# BrainA1-12n8.net
KiCad netlist of a schematic drawn in EAGLE
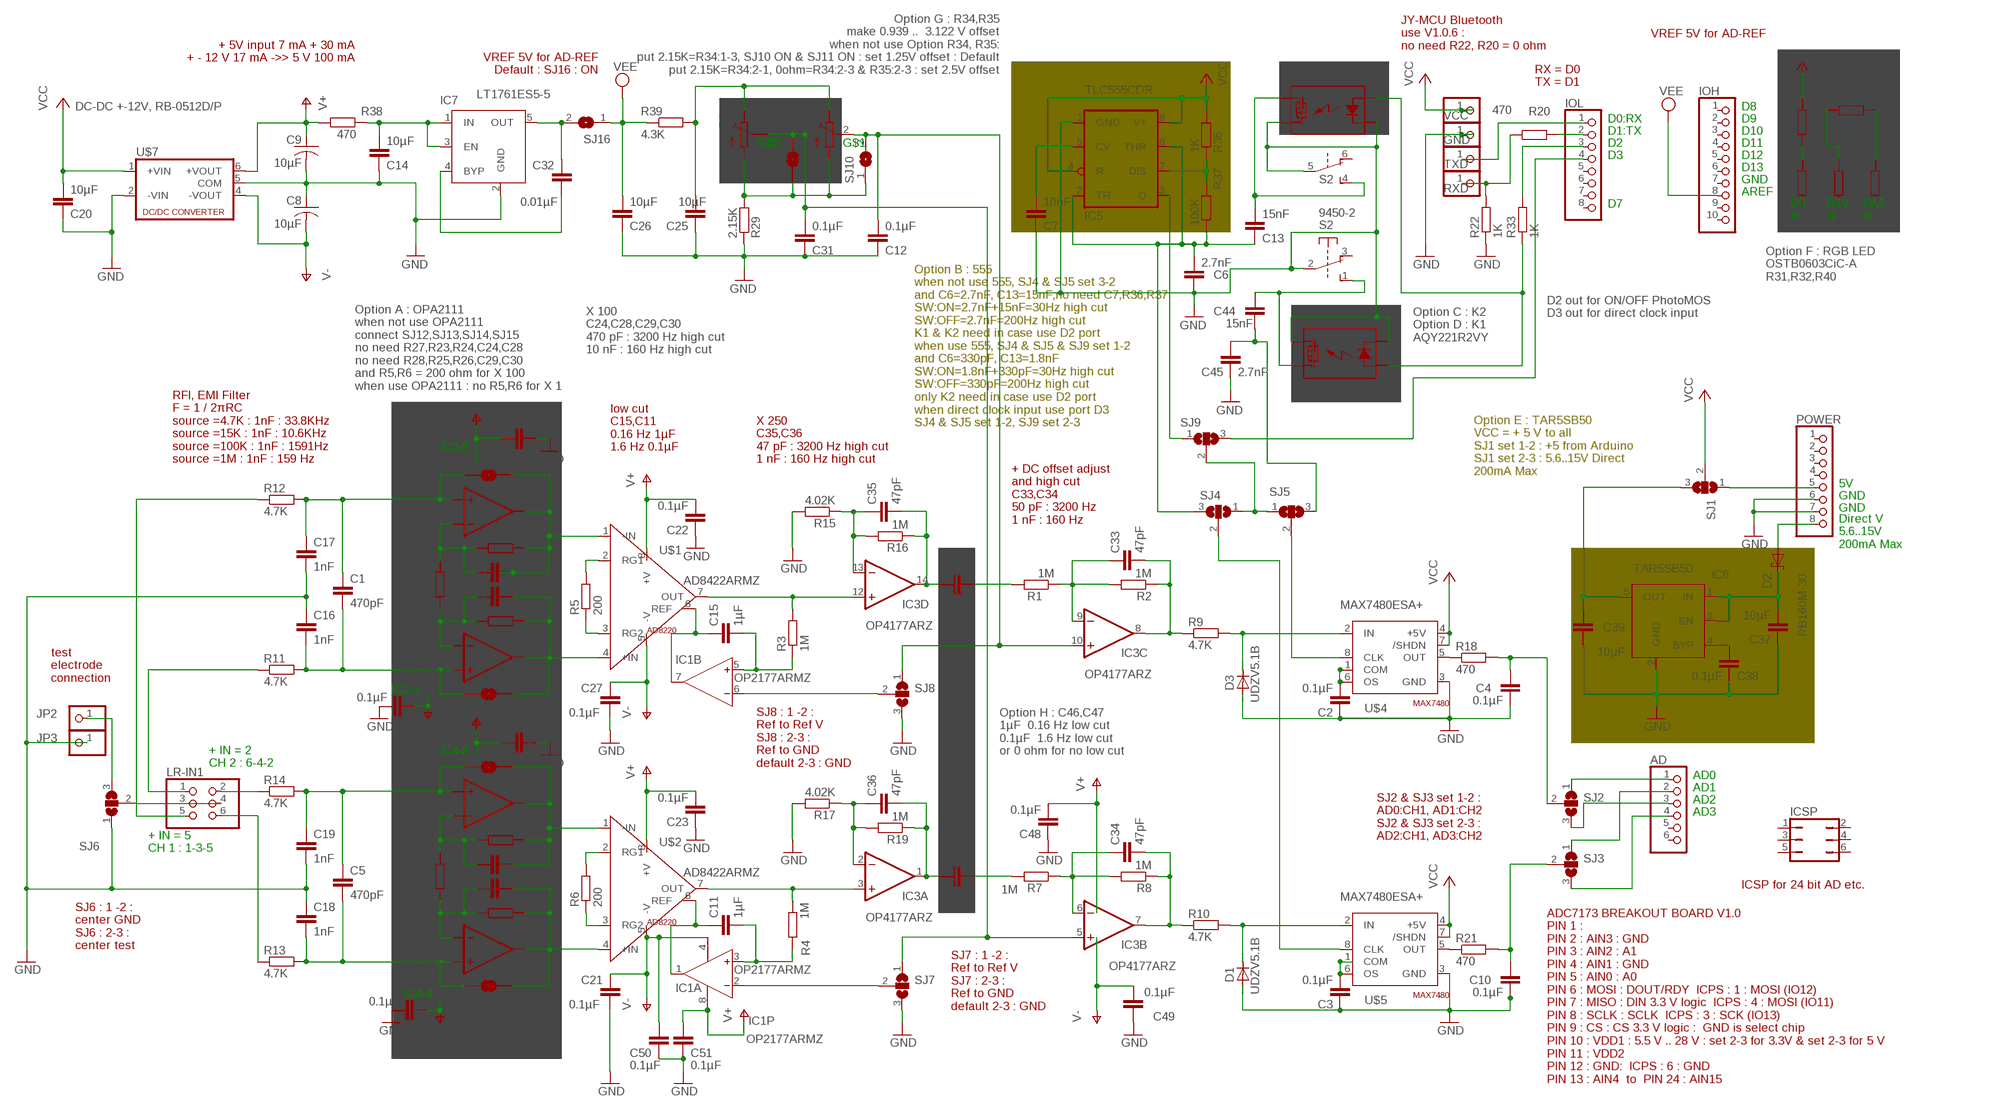
[diagram p0: schematic, sheet 1]

(export (version "E")
  (design (tool "Eeschema 10.0.6"))
  (components
    (comp (ref "AD")
      (value "PINHD-1X6")
      (footprint "eagle-import:1X06")
      (libsource (lib "eagle-import") (part "PINHD-1X6"))
    )
    (comp (ref "C1")
      (value "470pF")
      (footprint "eagle-import:C0805")
      (libsource (lib "eagle-import") (part "C-EUC0805"))
    )
    (comp (ref "C2")
      (value "0.1µF")
      (footprint "eagle-import:C0805")
      (libsource (lib "eagle-import") (part "C-EUC0805"))
    )
    (comp (ref "C3")
      (value "0.1µF")
      (footprint "eagle-import:C0805")
      (libsource (lib "eagle-import") (part "C-EUC0805"))
    )
    (comp (ref "C4")
      (value "0.1µF")
      (footprint "eagle-import:C0805")
      (libsource (lib "eagle-import") (part "C-EUC0805"))
    )
    (comp (ref "C5")
      (value "470pF")
      (footprint "eagle-import:C0805")
      (libsource (lib "eagle-import") (part "C-EUC0805"))
    )
    (comp (ref "C6")
      (value "2.7nF")
      (footprint "eagle-import:C0805")
      (libsource (lib "eagle-import") (part "C-EUC0805"))
    )
    (comp (ref "C7")
      (value "10nF")
      (footprint "eagle-import:C0805")
      (libsource (lib "eagle-import") (part "C-EUC0805"))
    )
    (comp (ref "C8")
      (value "10µF")
      (footprint "eagle-import:C0805")
      (libsource (lib "eagle-import") (part "C-USC0805"))
    )
    (comp (ref "C9")
      (value "10µF")
      (footprint "eagle-import:C0805")
      (libsource (lib "eagle-import") (part "C-USC0805"))
    )
    (comp (ref "C10")
      (value "0.1µF")
      (footprint "eagle-import:C0805")
      (libsource (lib "eagle-import") (part "C-EUC0805"))
    )
    (comp (ref "C11")
      (value "1µF")
      (footprint "eagle-import:C0805")
      (libsource (lib "eagle-import") (part "C-EUC0805"))
    )
    (comp (ref "C12")
      (value "0.1µF")
      (footprint "eagle-import:C0805")
      (libsource (lib "eagle-import") (part "C-EUC0805"))
    )
    (comp (ref "C13")
      (value "15nF")
      (footprint "eagle-import:C0805")
      (libsource (lib "eagle-import") (part "C-EUC0805"))
    )
    (comp (ref "C14")
      (value "10µF")
      (footprint "eagle-import:C0805")
      (libsource (lib "eagle-import") (part "C-EUC0805"))
    )
    (comp (ref "C15")
      (value "1µF")
      (footprint "eagle-import:C0805")
      (libsource (lib "eagle-import") (part "C-EUC0805"))
    )
    (comp (ref "C16")
      (value "1nF")
      (footprint "eagle-import:C0805")
      (libsource (lib "eagle-import") (part "C-EUC0805"))
    )
    (comp (ref "C17")
      (value "1nF")
      (footprint "eagle-import:C0805")
      (libsource (lib "eagle-import") (part "C-EUC0805"))
    )
    (comp (ref "C18")
      (value "1nF")
      (footprint "eagle-import:C0805")
      (libsource (lib "eagle-import") (part "C-EUC0805"))
    )
    (comp (ref "C19")
      (value "1nF")
      (footprint "eagle-import:C0805")
      (libsource (lib "eagle-import") (part "C-EUC0805"))
    )
    (comp (ref "C20")
      (value "10µF")
      (footprint "eagle-import:C0805")
      (libsource (lib "eagle-import") (part "C-EUC0805"))
    )
    (comp (ref "C21")
      (value "0.1µF")
      (footprint "eagle-import:C0805")
      (libsource (lib "eagle-import") (part "C-EUC0805"))
    )
    (comp (ref "C22")
      (value "0.1µF")
      (footprint "eagle-import:C0805")
      (libsource (lib "eagle-import") (part "C-EUC0805"))
    )
    (comp (ref "C23")
      (value "0.1µF")
      (footprint "eagle-import:C0805")
      (libsource (lib "eagle-import") (part "C-EUC0805"))
    )
    (comp (ref "C24")
      (value "470pF")
      (footprint "eagle-import:C0805")
      (libsource (lib "eagle-import") (part "C-EUC0805"))
    )
    (comp (ref "C25")
      (value "10µF")
      (footprint "eagle-import:C0805")
      (libsource (lib "eagle-import") (part "C-EUC0805"))
    )
    (comp (ref "C26")
      (value "10µF")
      (footprint "eagle-import:C0805")
      (libsource (lib "eagle-import") (part "C-EUC0805"))
    )
    (comp (ref "C27")
      (value "0.1µF")
      (footprint "eagle-import:C0805")
      (libsource (lib "eagle-import") (part "C-EUC0805"))
    )
    (comp (ref "C28")
      (value "470pF")
      (footprint "eagle-import:C0805")
      (libsource (lib "eagle-import") (part "C-EUC0805"))
    )
    (comp (ref "C29")
      (value "470pF")
      (footprint "eagle-import:C0805")
      (libsource (lib "eagle-import") (part "C-EUC0805"))
    )
    (comp (ref "C30")
      (value "470pF")
      (footprint "eagle-import:C0805")
      (libsource (lib "eagle-import") (part "C-EUC0805"))
    )
    (comp (ref "C31")
      (value "0.1µF")
      (footprint "eagle-import:C0805")
      (libsource (lib "eagle-import") (part "C-EUC0805"))
    )
    (comp (ref "C32")
      (value "0.01µF")
      (footprint "eagle-import:C0805")
      (libsource (lib "eagle-import") (part "C-EUC0805"))
    )
    (comp (ref "C33")
      (value "47pF")
      (footprint "eagle-import:C0805")
      (libsource (lib "eagle-import") (part "C-EUC0805"))
    )
    (comp (ref "C34")
      (value "47pF")
      (footprint "eagle-import:C0805")
      (libsource (lib "eagle-import") (part "C-EUC0805"))
    )
    (comp (ref "C35")
      (value "47pF")
      (footprint "eagle-import:C0805")
      (libsource (lib "eagle-import") (part "C-EUC0805"))
    )
    (comp (ref "C36")
      (value "47pF")
      (footprint "eagle-import:C0805")
      (libsource (lib "eagle-import") (part "C-EUC0805"))
    )
    (comp (ref "C37")
      (value "10µF")
      (footprint "eagle-import:C0805")
      (libsource (lib "eagle-import") (part "C-EUC0805"))
    )
    (comp (ref "C38")
      (value "0.1µF")
      (footprint "eagle-import:C0805")
      (libsource (lib "eagle-import") (part "C-EUC0805"))
    )
    (comp (ref "C39")
      (value "10µF")
      (footprint "eagle-import:C0805")
      (libsource (lib "eagle-import") (part "C-EUC0805"))
    )
    (comp (ref "C40")
      (value "0.1µF")
      (footprint "eagle-import:C0805")
      (libsource (lib "eagle-import") (part "C-EUC0805"))
    )
    (comp (ref "C41")
      (value "0.1µF")
      (footprint "eagle-import:C0805")
      (libsource (lib "eagle-import") (part "C-EUC0805"))
    )
    (comp (ref "C42")
      (value "0.1µF")
      (footprint "eagle-import:C0805")
      (libsource (lib "eagle-import") (part "C-EUC0805"))
    )
    (comp (ref "C43")
      (value "0.1µF")
      (footprint "eagle-import:C0805")
      (libsource (lib "eagle-import") (part "C-EUC0805"))
    )
    (comp (ref "C44")
      (value "15nF")
      (footprint "eagle-import:C0805")
      (libsource (lib "eagle-import") (part "C-EUC0805"))
    )
    (comp (ref "C45")
      (value "2.7nF")
      (footprint "eagle-import:C0805")
      (libsource (lib "eagle-import") (part "C-EUC0805"))
    )
    (comp (ref "C46")
      (value "1µF")
      (footprint "eagle-import:C0805")
      (libsource (lib "eagle-import") (part "C-EUC0805"))
    )
    (comp (ref "C47")
      (value "1µF")
      (footprint "eagle-import:C0805")
      (libsource (lib "eagle-import") (part "C-EUC0805"))
    )
    (comp (ref "C48")
      (value "0.1µF")
      (footprint "eagle-import:C0805")
      (libsource (lib "eagle-import") (part "C-EUC0805"))
    )
    (comp (ref "C49")
      (value "0.1µF")
      (footprint "eagle-import:C0805")
      (libsource (lib "eagle-import") (part "C-EUC0805"))
    )
    (comp (ref "C50")
      (value "0.1µF")
      (footprint "eagle-import:C0805")
      (libsource (lib "eagle-import") (part "C-EUC0805"))
    )
    (comp (ref "C51")
      (value "0.1µF")
      (footprint "eagle-import:C0805")
      (libsource (lib "eagle-import") (part "C-EUC0805"))
    )
    (comp (ref "D1")
      (value "UDZV5.1B")
      (footprint "eagle-import:SOD110-R")
      (libsource (lib "eagle-import") (part "DIODE-SOD110-R"))
    )
    (comp (ref "D2")
      (value "RB160M-30")
      (footprint "eagle-import:POWERDI323")
      (libsource (lib "eagle-import") (part "PD3S160"))
    )
    (comp (ref "D3")
      (value "UDZV5.1B")
      (footprint "eagle-import:SOD110-R")
      (libsource (lib "eagle-import") (part "DIODE-SOD110-R"))
    )
    (comp (ref "GND")
      (value "PINHD-1X1")
      (footprint "eagle-import:1X01")
      (libsource (lib "eagle-import") (part "PINHD-1X1"))
    )
    (comp (ref "IC1")
      (value "OP2177ARMZ")
      (footprint "eagle-import:MSOP08")
      (fields (field (name "MPN") "AD8656ARMZ"))
      (libsource (lib "eagle-import") (part "AD8656RM"))
    )
    (comp (ref "IC2")
      (value "OPA2111KP")
      (footprint "eagle-import:DIL08")
      (libsource (lib "eagle-import") (part "OPA2111P"))
    )
    (comp (ref "IC3")
      (value "OP4177ARZ")
      (footprint "eagle-import:SO14")
      (libsource (lib "eagle-import") (part "TL064D"))
    )
    (comp (ref "IC4")
      (value "OPA2111KP")
      (footprint "eagle-import:DIL08")
      (libsource (lib "eagle-import") (part "OPA2111P"))
    )
    (comp (ref "IC5")
      (value "TLC555CDR")
      (footprint "eagle-import:SO08")
      (libsource (lib "eagle-import") (part "555DLM"))
    )
    (comp (ref "IC6")
      (value "TAR5SB50")
      (footprint "eagle-import:SOT23-5")
      (libsource (lib "eagle-import") (part "MIC5219XX"))
    )
    (comp (ref "IC7")
      (value "LT1761ES5-5")
      (footprint "eagle-import:SOT23-5")
      (libsource (lib "eagle-import") (part "MIC5219XX"))
    )
    (comp (ref "ICSP")
      (value "JP3Q")
      (footprint "eagle-import:JP3Q")
      (libsource (lib "eagle-import") (part "JP3Q"))
    )
    (comp (ref "IOH")
      (value "PINHD-1X10")
      (footprint "eagle-import:1X10")
      (libsource (lib "eagle-import") (part "PINHD-1X10"))
    )
    (comp (ref "IOL")
      (value "PINHD-1X8")
      (footprint "eagle-import:1X08")
      (libsource (lib "eagle-import") (part "PINHD-1X8"))
    )
    (comp (ref "JP2")
      (value "PINHD-1X1")
      (footprint "eagle-import:1X01")
      (libsource (lib "eagle-import") (part "PINHD-1X1"))
    )
    (comp (ref "JP3")
      (value "PINHD-1X1")
      (footprint "eagle-import:1X01")
      (libsource (lib "eagle-import") (part "PINHD-1X1"))
    )
    (comp (ref "K1")
      (value "AQY221R2VY")
      (footprint "eagle-import:SSOP4")
      (fields (field (name "MF") "AROMAT/ MATSUSHITA") (field (name "MPN") "AQY221R2V"))
      (libsource (lib "eagle-import") (part "AQY2212VR"))
    )
    (comp (ref "K2")
      (value "AQY221R2VY")
      (footprint "eagle-import:SSOP4")
      (fields (field (name "MF") "AROMAT/ MATSUSHITA") (field (name "MPN") "AQY221R2V"))
      (libsource (lib "eagle-import") (part "AQY2212VR"))
    )
    (comp (ref "LR-IN1")
      (value "PINHD-2X3/90")
      (footprint "eagle-import:2X03_90")
      (libsource (lib "eagle-import") (part "PINHD-2X3/90"))
    )
    (comp (ref "POWER")
      (value "PINHD-1X8")
      (footprint "eagle-import:1X08")
      (libsource (lib "eagle-import") (part "PINHD-1X8"))
    )
    (comp (ref "R1")
      (value "1M")
      (footprint "eagle-import:R0805")
      (libsource (lib "eagle-import") (part "R-EU_R0805"))
    )
    (comp (ref "R2")
      (value "1M")
      (footprint "eagle-import:R0805")
      (libsource (lib "eagle-import") (part "R-EU_R0805"))
    )
    (comp (ref "R3")
      (value "1M")
      (footprint "eagle-import:R0805")
      (libsource (lib "eagle-import") (part "R-EU_R0805"))
    )
    (comp (ref "R4")
      (value "1M")
      (footprint "eagle-import:R0805")
      (libsource (lib "eagle-import") (part "R-EU_R0805"))
    )
    (comp (ref "R5")
      (value "200")
      (footprint "eagle-import:R0805")
      (libsource (lib "eagle-import") (part "R-EU_R0805"))
    )
    (comp (ref "R6")
      (value "200")
      (footprint "eagle-import:R0805")
      (libsource (lib "eagle-import") (part "R-EU_R0805"))
    )
    (comp (ref "R7")
      (value "1M")
      (footprint "eagle-import:R0805")
      (libsource (lib "eagle-import") (part "R-EU_R0805"))
    )
    (comp (ref "R8")
      (value "1M")
      (footprint "eagle-import:R0805")
      (libsource (lib "eagle-import") (part "R-EU_R0805"))
    )
    (comp (ref "R9")
      (value "4.7K")
      (footprint "eagle-import:R0805")
      (libsource (lib "eagle-import") (part "R-EU_R0805"))
    )
    (comp (ref "R10")
      (value "4.7K")
      (footprint "eagle-import:R0805")
      (libsource (lib "eagle-import") (part "R-EU_R0805"))
    )
    (comp (ref "R11")
      (value "4.7K")
      (footprint "eagle-import:R0805")
      (libsource (lib "eagle-import") (part "R-EU_R0805"))
    )
    (comp (ref "R12")
      (value "4.7K")
      (footprint "eagle-import:R0805")
      (libsource (lib "eagle-import") (part "R-EU_R0805"))
    )
    (comp (ref "R13")
      (value "4.7K")
      (footprint "eagle-import:R0805")
      (libsource (lib "eagle-import") (part "R-EU_R0805"))
    )
    (comp (ref "R14")
      (value "4.7K")
      (footprint "eagle-import:R0805")
      (libsource (lib "eagle-import") (part "R-EU_R0805"))
    )
    (comp (ref "R15")
      (value "4.02K")
      (footprint "eagle-import:R0805")
      (libsource (lib "eagle-import") (part "R-EU_R0805"))
    )
    (comp (ref "R16")
      (value "1M")
      (footprint "eagle-import:R0805")
      (libsource (lib "eagle-import") (part "R-EU_R0805"))
    )
    (comp (ref "R17")
      (value "4.02K")
      (footprint "eagle-import:R0805")
      (libsource (lib "eagle-import") (part "R-EU_R0805"))
    )
    (comp (ref "R18")
      (value "470")
      (footprint "eagle-import:R0805")
      (libsource (lib "eagle-import") (part "R-EU_R0805"))
    )
    (comp (ref "R19")
      (value "1M")
      (footprint "eagle-import:R0805")
      (libsource (lib "eagle-import") (part "R-EU_R0805"))
    )
    (comp (ref "R20")
      (value "470")
      (footprint "eagle-import:R0805")
      (libsource (lib "eagle-import") (part "R-EU_R0805"))
    )
    (comp (ref "R21")
      (value "470")
      (footprint "eagle-import:R0805")
      (libsource (lib "eagle-import") (part "R-EU_R0805"))
    )
    (comp (ref "R22")
      (value "1K")
      (footprint "eagle-import:R0805")
      (libsource (lib "eagle-import") (part "R-EU_R0805"))
    )
    (comp (ref "R23")
      (value "100K")
      (footprint "eagle-import:R0805")
      (libsource (lib "eagle-import") (part "R-EU_R0805"))
    )
    (comp (ref "R24")
      (value "100K")
      (footprint "eagle-import:R0805")
      (libsource (lib "eagle-import") (part "R-EU_R0805"))
    )
    (comp (ref "R25")
      (value "100K")
      (footprint "eagle-import:R0805")
      (libsource (lib "eagle-import") (part "R-EU_R0805"))
    )
    (comp (ref "R26")
      (value "100K")
      (footprint "eagle-import:R0805")
      (libsource (lib "eagle-import") (part "R-EU_R0805"))
    )
    (comp (ref "R27")
      (value "2K")
      (footprint "eagle-import:R0805")
      (libsource (lib "eagle-import") (part "R-EU_R0805"))
    )
    (comp (ref "R28")
      (value "2K")
      (footprint "eagle-import:R0805")
      (libsource (lib "eagle-import") (part "R-EU_R0805"))
    )
    (comp (ref "R29")
      (value "2.15K")
      (footprint "eagle-import:R0805")
      (libsource (lib "eagle-import") (part "R-EU_R0805"))
    )
    (comp (ref "R30")
      (value "LED")
      (footprint "eagle-import:R0402")
      (libsource (lib "eagle-import") (part "R-EU_R0402"))
    )
    (comp (ref "R31")
      (value "1K")
      (footprint "eagle-import:R0402")
      (libsource (lib "eagle-import") (part "R-EU_R0402"))
    )
    (comp (ref "R32")
      (value "1K")
      (footprint "eagle-import:R0402")
      (libsource (lib "eagle-import") (part "R-EU_R0402"))
    )
    (comp (ref "R33")
      (value "1K")
      (footprint "eagle-import:R0805")
      (libsource (lib "eagle-import") (part "R-EU_R0805"))
    )
    (comp (ref "R34")
      (value "10K")
      (footprint "eagle-import:RTRIM5X")
      (libsource (lib "eagle-import") (part "R-TRIMM5X"))
    )
    (comp (ref "R35")
      (value "10K")
      (footprint "eagle-import:RTRIM5X")
      (libsource (lib "eagle-import") (part "R-TRIMM5X"))
    )
    (comp (ref "R36")
      (value "1K")
      (footprint "eagle-import:R0805")
      (libsource (lib "eagle-import") (part "R-EU_R0805"))
    )
    (comp (ref "R37")
      (value "100K")
      (footprint "eagle-import:R0805")
      (libsource (lib "eagle-import") (part "R-EU_R0805"))
    )
    (comp (ref "R38")
      (value "470")
      (footprint "eagle-import:R0805")
      (libsource (lib "eagle-import") (part "R-EU_R0805"))
    )
    (comp (ref "R39")
      (value "4.3K")
      (footprint "eagle-import:R0805")
      (libsource (lib "eagle-import") (part "R-EU_R0805"))
    )
    (comp (ref "R40")
      (value "1K")
      (footprint "eagle-import:R0402")
      (libsource (lib "eagle-import") (part "R-EU_R0402"))
    )
    (comp (ref "R41")
      (value "LED")
      (footprint "eagle-import:R0402")
      (libsource (lib "eagle-import") (part "R-EU_R0402"))
    )
    (comp (ref "RXD")
      (value "PINHD-1X1")
      (footprint "eagle-import:1X01")
      (libsource (lib "eagle-import") (part "PINHD-1X1"))
    )
    (comp (ref "S2")
      (value "9450-2")
      (footprint "eagle-import:9450-2")
      (libsource (lib "eagle-import") (part "9450-2"))
    )
    (comp (ref "SJ1")
      (value "SJ2W")
      (footprint "eagle-import:SJ_2")
      (libsource (lib "eagle-import") (part "SJ2W"))
    )
    (comp (ref "SJ2")
      (value "SJ2W")
      (footprint "eagle-import:SJ_2")
      (libsource (lib "eagle-import") (part "SJ2W"))
    )
    (comp (ref "SJ3")
      (value "SJ2W")
      (footprint "eagle-import:SJ_2")
      (libsource (lib "eagle-import") (part "SJ2W"))
    )
    (comp (ref "SJ4")
      (value "SJ2W")
      (footprint "eagle-import:SJ_2")
      (libsource (lib "eagle-import") (part "SJ2W"))
    )
    (comp (ref "SJ5")
      (value "SJ2W")
      (footprint "eagle-import:SJ_2")
      (libsource (lib "eagle-import") (part "SJ2W"))
    )
    (comp (ref "SJ6")
      (value "SJ2W")
      (footprint "eagle-import:SJ_2")
      (libsource (lib "eagle-import") (part "SJ2W"))
    )
    (comp (ref "SJ7")
      (value "SJ2W")
      (footprint "eagle-import:SJ_2")
      (libsource (lib "eagle-import") (part "SJ2W"))
    )
    (comp (ref "SJ8")
      (value "SJ2W")
      (footprint "eagle-import:SJ_2")
      (libsource (lib "eagle-import") (part "SJ2W"))
    )
    (comp (ref "SJ9")
      (value "SJ2W")
      (footprint "eagle-import:SJ_2")
      (libsource (lib "eagle-import") (part "SJ2W"))
    )
    (comp (ref "SJ10")
      (value "SJ")
      (footprint "eagle-import:SJ")
      (libsource (lib "eagle-import") (part "SJ"))
    )
    (comp (ref "SJ11")
      (value "SJ")
      (footprint "eagle-import:SJ")
      (libsource (lib "eagle-import") (part "SJ"))
    )
    (comp (ref "SJ12")
      (value "SJ")
      (footprint "eagle-import:SJ")
      (libsource (lib "eagle-import") (part "SJ"))
    )
    (comp (ref "SJ13")
      (value "SJ")
      (footprint "eagle-import:SJ")
      (libsource (lib "eagle-import") (part "SJ"))
    )
    (comp (ref "SJ14")
      (value "SJ")
      (footprint "eagle-import:SJ")
      (libsource (lib "eagle-import") (part "SJ"))
    )
    (comp (ref "SJ15")
      (value "SJ")
      (footprint "eagle-import:SJ")
      (libsource (lib "eagle-import") (part "SJ"))
    )
    (comp (ref "SJ16")
      (value "SJ")
      (footprint "eagle-import:SJ")
      (libsource (lib "eagle-import") (part "SJ"))
    )
    (comp (ref "TXD")
      (value "PINHD-1X1")
      (footprint "eagle-import:1X01")
      (libsource (lib "eagle-import") (part "PINHD-1X1"))
    )
    (comp (ref "U$1")
      (value "AD8422ARMZ")
      (footprint "eagle-import:AD8220")
      (libsource (lib "eagle-import") (part "AD8220"))
    )
    (comp (ref "U$2")
      (value "AD8422ARMZ")
      (footprint "eagle-import:AD8220")
      (libsource (lib "eagle-import") (part "AD8220"))
    )
    (comp (ref "U$4")
      (value "MAX7480ESA+")
      (footprint "eagle-import:MAX7480")
      (libsource (lib "eagle-import") (part "MAX7480"))
    )
    (comp (ref "U$5")
      (value "MAX7480ESA+")
      (footprint "eagle-import:MAX7480")
      (libsource (lib "eagle-import") (part "MAX7480"))
    )
    (comp (ref "U$7")
      (value "DC-DC +-12V, RB-0512D/P")
      (footprint "eagle-import:RB-0515D")
      (libsource (lib "eagle-import") (part "RB-0515D"))
    )
    (comp (ref "VCC")
      (value "PINHD-1X1")
      (footprint "eagle-import:1X01")
      (libsource (lib "eagle-import") (part "PINHD-1X1"))
    )
  )
  (nets
    (net (code "1") (name "GND") (class "Default")
      (node (ref "C10") (pin "1") (pinfunction "1_1") (pintype "passive"))
      (node (ref "C12") (pin "1") (pinfunction "1_1") (pintype "passive"))
      (node (ref "C14") (pin "1") (pinfunction "1_1") (pintype "passive"))
      (node (ref "C16") (pin "1") (pinfunction "1_1") (pintype "passive"))
      (node (ref "C17") (pin "2") (pinfunction "2_2") (pintype "passive"))
      (node (ref "C18") (pin "1") (pinfunction "1_1") (pintype "passive"))
      (node (ref "C19") (pin "2") (pinfunction "2_2") (pintype "passive"))
      (node (ref "C2") (pin "1") (pinfunction "1_1") (pintype "passive"))
      (node (ref "C20") (pin "1") (pinfunction "1_1") (pintype "passive"))
      (node (ref "C21") (pin "2") (pinfunction "2_2") (pintype "passive"))
      (node (ref "C22") (pin "1") (pinfunction "1_1") (pintype "passive"))
      (node (ref "C23") (pin "1") (pinfunction "1_1") (pintype "passive"))
      (node (ref "C25") (pin "1") (pinfunction "1_1") (pintype "passive"))
      (node (ref "C26") (pin "1") (pinfunction "1_1") (pintype "passive"))
      (node (ref "C27") (pin "2") (pinfunction "2_2") (pintype "passive"))
      (node (ref "C3") (pin "1") (pinfunction "1_1") (pintype "passive"))
      (node (ref "C31") (pin "1") (pinfunction "1_1") (pintype "passive"))
      (node (ref "C37") (pin "1") (pinfunction "1_1") (pintype "passive"))
      (node (ref "C38") (pin "1") (pinfunction "1_1") (pintype "passive"))
      (node (ref "C39") (pin "1") (pinfunction "1_1") (pintype "passive"))
      (node (ref "C4") (pin "1") (pinfunction "1_1") (pintype "passive"))
      (node (ref "C40") (pin "1") (pinfunction "1_1") (pintype "passive"))
      (node (ref "C41") (pin "2") (pinfunction "2_2") (pintype "passive"))
      (node (ref "C42") (pin "2") (pinfunction "2_2") (pintype "passive"))
      (node (ref "C43") (pin "2") (pinfunction "2_2") (pintype "passive"))
      (node (ref "C45") (pin "1") (pinfunction "1_1") (pintype "passive"))
      (node (ref "C48") (pin "1") (pinfunction "1_1") (pintype "passive"))
      (node (ref "C49") (pin "1") (pinfunction "1_1") (pintype "passive"))
      (node (ref "C50") (pin "2") (pinfunction "2_2") (pintype "passive"))
      (node (ref "C51") (pin "2") (pinfunction "2_2") (pintype "passive"))
      (node (ref "C6") (pin "1") (pinfunction "1_1") (pintype "passive"))
      (node (ref "C7") (pin "1") (pinfunction "1_1") (pintype "passive"))
      (node (ref "C8") (pin "1") (pinfunction "1_1") (pintype "passive"))
      (node (ref "C9") (pin "2") (pinfunction "2_2") (pintype "passive"))
      (node (ref "D1") (pin "A") (pinfunction "A_A") (pintype "passive"))
      (node (ref "D3") (pin "A") (pinfunction "A_A") (pintype "passive"))
      (node (ref "GND") (pin "1") (pinfunction "1_1") (pintype "passive"))
      (node (ref "IC5") (pin "1") (pinfunction "GND_1") (pintype "power_in"))
      (node (ref "IC6") (pin "2") (pinfunction "GND_2") (pintype "power_in"))
      (node (ref "IC7") (pin "2") (pinfunction "GND_2") (pintype "power_in"))
      (node (ref "JP3") (pin "1") (pinfunction "1_1") (pintype "passive"))
      (node (ref "K1") (pin "2") (pinfunction "K_2") (pintype "passive"))
      (node (ref "K1") (pin "3") (pinfunction "DS2_3") (pintype "passive"))
      (node (ref "K2") (pin "2") (pinfunction "K_2") (pintype "passive"))
      (node (ref "K2") (pin "3") (pinfunction "DS2_3") (pintype "passive"))
      (node (ref "POWER") (pin "6") (pinfunction "6_6") (pintype "passive"))
      (node (ref "POWER") (pin "7") (pinfunction "7_7") (pintype "passive"))
      (node (ref "R15") (pin "2") (pinfunction "2_2") (pintype "passive"))
      (node (ref "R17") (pin "2") (pinfunction "2_2") (pintype "passive"))
      (node (ref "R22") (pin "1") (pinfunction "1_1") (pintype "passive"))
      (node (ref "R29") (pin "1") (pinfunction "1_1") (pintype "passive"))
      (node (ref "S2") (pin "2") (pinfunction "P_2") (pintype "passive"))
      (node (ref "S2") (pin "5") (pinfunction "P_5") (pintype "passive"))
      (node (ref "SJ6") (pin "1") (pinfunction "1_1") (pintype "passive"))
      (node (ref "SJ7") (pin "3") (pinfunction "3_3") (pintype "passive"))
      (node (ref "SJ8") (pin "3") (pinfunction "3_3") (pintype "passive"))
      (node (ref "U$4") (pin "3") (pinfunction "GND_3") (pintype "power_in"))
      (node (ref "U$5") (pin "3") (pinfunction "GND_3") (pintype "power_in"))
      (node (ref "U$7") (pin "2") (pinfunction "-VIN_2") (pintype "passive"))
      (node (ref "U$7") (pin "5") (pinfunction "COM_5") (pintype "passive"))
    )
    (net (code "2") (name "Net-(AD-Pad1)") (class "Default")
      (node (ref "AD") (pin "1") (pinfunction "1_1") (pintype "passive"))
      (node (ref "SJ2") (pin "1") (pinfunction "1_1") (pintype "passive"))
    )
    (net (code "3") (name "Net-(AD-Pad2)") (class "Default")
      (node (ref "AD") (pin "2") (pinfunction "2_2") (pintype "passive"))
      (node (ref "SJ3") (pin "1") (pinfunction "1_1") (pintype "passive"))
    )
    (net (code "4") (name "Net-(AD-Pad3)") (class "Default")
      (node (ref "AD") (pin "3") (pinfunction "3_3") (pintype "passive"))
      (node (ref "SJ2") (pin "3") (pinfunction "3_3") (pintype "passive"))
    )
    (net (code "5") (name "Net-(AD-Pad4)") (class "Default")
      (node (ref "AD") (pin "4") (pinfunction "4_4") (pintype "passive"))
      (node (ref "SJ3") (pin "3") (pinfunction "3_3") (pintype "passive"))
    )
    (net (code "6") (name "Net-(C4-Pad2)") (class "Default")
      (node (ref "C4") (pin "2") (pinfunction "2_2") (pintype "passive"))
      (node (ref "R18") (pin "2") (pinfunction "2_2") (pintype "passive"))
      (node (ref "SJ2") (pin "2") (pinfunction "2_2") (pintype "passive"))
    )
    (net (code "7") (name "Net-(C10-Pad2)") (class "Default")
      (node (ref "C10") (pin "2") (pinfunction "2_2") (pintype "passive"))
      (node (ref "R21") (pin "2") (pinfunction "2_2") (pintype "passive"))
      (node (ref "SJ3") (pin "2") (pinfunction "2_2") (pintype "passive"))
    )
    (net (code "8") (name "Net-(C44-Pad1)") (class "Default")
      (node (ref "C44") (pin "1") (pinfunction "1_1") (pintype "passive"))
      (node (ref "C45") (pin "2") (pinfunction "2_2") (pintype "passive"))
      (node (ref "SJ5") (pin "3") (pinfunction "3_3") (pintype "passive"))
    )
    (net (code "9") (name "Net-(C46-Pad2)") (class "Default")
      (node (ref "C46") (pin "2") (pinfunction "2_2") (pintype "passive"))
      (node (ref "R1") (pin "2") (pinfunction "2_2") (pintype "passive"))
    )
    (net (code "10") (name "Net-(C47-Pad2)") (class "Default")
      (node (ref "C47") (pin "2") (pinfunction "2_2") (pintype "passive"))
      (node (ref "R7") (pin "2") (pinfunction "2_2") (pintype "passive"))
    )
    (net (code "11") (name "Net-(D2-PadA)") (class "Default")
      (node (ref "D2") (pin "A") (pinfunction "A_A") (pintype "passive"))
      (node (ref "POWER") (pin "8") (pinfunction "8_8") (pintype "passive"))
    )
    (net (code "12") (name "Net-(IC1A-IN+)") (class "Default")
      (node (ref "C11") (pin "2") (pinfunction "2_2") (pintype "passive"))
      (node (ref "IC1") (pin "3") (pinfunction "IN+_3") (pintype "input"))
      (node (ref "R4") (pin "1") (pinfunction "1_1") (pintype "passive"))
    )
    (net (code "13") (name "Net-(IC1A-IN-)") (class "Default")
      (node (ref "IC1") (pin "2") (pinfunction "IN-_2") (pintype "input"))
      (node (ref "SJ7") (pin "2") (pinfunction "2_2") (pintype "passive"))
    )
    (net (code "14") (name "Net-(IC1A-OUT)") (class "Default")
      (node (ref "C11") (pin "1") (pinfunction "1_1") (pintype "passive"))
      (node (ref "IC1") (pin "1") (pinfunction "OUT_1") (pintype "output"))
      (node (ref "U$2") (pin "6") (pinfunction "REF_6") (pintype "input"))
    )
    (net (code "15") (name "Net-(IC1B-IN+)") (class "Default")
      (node (ref "C15") (pin "2") (pinfunction "2_2") (pintype "passive"))
      (node (ref "IC1") (pin "5") (pinfunction "IN+_5") (pintype "input"))
      (node (ref "R3") (pin "1") (pinfunction "1_1") (pintype "passive"))
    )
    (net (code "16") (name "Net-(IC1B-IN-)") (class "Default")
      (node (ref "IC1") (pin "6") (pinfunction "IN-_6") (pintype "input"))
      (node (ref "SJ8") (pin "2") (pinfunction "2_2") (pintype "passive"))
    )
    (net (code "17") (name "Net-(IC1B-OUT)") (class "Default")
      (node (ref "C15") (pin "1") (pinfunction "1_1") (pintype "passive"))
      (node (ref "IC1") (pin "7") (pinfunction "OUT_7") (pintype "output"))
      (node (ref "U$1") (pin "6") (pinfunction "REF_6") (pintype "input"))
    )
    (net (code "18") (name "Net-(IC2A-+IN)") (class "Default")
      (node (ref "C1") (pin "1") (pinfunction "1_1") (pintype "passive"))
      (node (ref "C17") (pin "1") (pinfunction "1_1") (pintype "passive"))
      (node (ref "IC2") (pin "3") (pinfunction "+IN_3") (pintype "input"))
      (node (ref "R12") (pin "2") (pinfunction "2_2") (pintype "passive"))
      (node (ref "SJ12") (pin "2") (pinfunction "2_2") (pintype "passive"))
    )
    (net (code "19") (name "Net-(IC2A--IN)") (class "Default")
      (node (ref "C24") (pin "1") (pinfunction "1_1") (pintype "passive"))
      (node (ref "IC2") (pin "2") (pinfunction "-IN_2") (pintype "input"))
      (node (ref "R23") (pin "1") (pinfunction "1_1") (pintype "passive"))
      (node (ref "R27") (pin "2") (pinfunction "2_2") (pintype "passive"))
    )
    (net (code "20") (name "Net-(IC2A-OUT)") (class "Default")
      (node (ref "C24") (pin "2") (pinfunction "2_2") (pintype "passive"))
      (node (ref "IC2") (pin "1") (pinfunction "OUT_1") (pintype "output"))
      (node (ref "R23") (pin "2") (pinfunction "2_2") (pintype "passive"))
      (node (ref "SJ12") (pin "1") (pinfunction "1_1") (pintype "passive"))
      (node (ref "U$1") (pin "1") (pinfunction "-IN_1") (pintype "input"))
    )
    (net (code "21") (name "Net-(IC2B-+IN)") (class "Default")
      (node (ref "C1") (pin "2") (pinfunction "2_2") (pintype "passive"))
      (node (ref "C16") (pin "2") (pinfunction "2_2") (pintype "passive"))
      (node (ref "IC2") (pin "5") (pinfunction "+IN_5") (pintype "input"))
      (node (ref "R11") (pin "2") (pinfunction "2_2") (pintype "passive"))
      (node (ref "SJ13") (pin "2") (pinfunction "2_2") (pintype "passive"))
    )
    (net (code "22") (name "Net-(IC2B--IN)") (class "Default")
      (node (ref "C28") (pin "1") (pinfunction "1_1") (pintype "passive"))
      (node (ref "IC2") (pin "6") (pinfunction "-IN_6") (pintype "input"))
      (node (ref "R24") (pin "1") (pinfunction "1_1") (pintype "passive"))
      (node (ref "R27") (pin "1") (pinfunction "1_1") (pintype "passive"))
    )
    (net (code "23") (name "Net-(IC2B-OUT)") (class "Default")
      (node (ref "C28") (pin "2") (pinfunction "2_2") (pintype "passive"))
      (node (ref "IC2") (pin "7") (pinfunction "OUT_7") (pintype "output"))
      (node (ref "R24") (pin "2") (pinfunction "2_2") (pintype "passive"))
      (node (ref "SJ13") (pin "1") (pinfunction "1_1") (pintype "passive"))
      (node (ref "U$1") (pin "4") (pinfunction "+IN_4") (pintype "passive"))
    )
    (net (code "24") (name "Net-(IC3A-+IN)") (class "Default")
      (node (ref "IC3") (pin "3") (pinfunction "+IN_3") (pintype "input"))
      (node (ref "R4") (pin "2") (pinfunction "2_2") (pintype "passive"))
      (node (ref "U$2") (pin "7") (pinfunction "OUT_7") (pintype "input"))
    )
    (net (code "25") (name "Net-(IC3A--IN)") (class "Default")
      (node (ref "C36") (pin "1") (pinfunction "1_1") (pintype "passive"))
      (node (ref "IC3") (pin "2") (pinfunction "-IN_2") (pintype "input"))
      (node (ref "R17") (pin "1") (pinfunction "1_1") (pintype "passive"))
      (node (ref "R19") (pin "2") (pinfunction "2_2") (pintype "passive"))
    )
    (net (code "26") (name "Net-(IC3A-OUT)") (class "Default")
      (node (ref "C36") (pin "2") (pinfunction "2_2") (pintype "passive"))
      (node (ref "C47") (pin "1") (pinfunction "1_1") (pintype "passive"))
      (node (ref "IC3") (pin "1") (pinfunction "OUT_1") (pintype "output"))
      (node (ref "R19") (pin "1") (pinfunction "1_1") (pintype "passive"))
    )
    (net (code "27") (name "Net-(IC3B-+IN)") (class "Default")
      (node (ref "C31") (pin "2") (pinfunction "2_2") (pintype "passive"))
      (node (ref "IC3") (pin "5") (pinfunction "+IN_5") (pintype "input"))
      (node (ref "R34") (pin "2") (pinfunction "S_2") (pintype "passive"))
      (node (ref "SJ11") (pin "2") (pinfunction "2_2") (pintype "passive"))
      (node (ref "SJ7") (pin "1") (pinfunction "1_1") (pintype "passive"))
    )
    (net (code "28") (name "Net-(IC3B--IN)") (class "Default")
      (node (ref "C34") (pin "1") (pinfunction "1_1") (pintype "passive"))
      (node (ref "IC3") (pin "6") (pinfunction "-IN_6") (pintype "input"))
      (node (ref "R7") (pin "1") (pinfunction "1_1") (pintype "passive"))
      (node (ref "R8") (pin "2") (pinfunction "2_2") (pintype "passive"))
    )
    (net (code "29") (name "Net-(IC3B-OUT)") (class "Default")
      (node (ref "C34") (pin "2") (pinfunction "2_2") (pintype "passive"))
      (node (ref "IC3") (pin "7") (pinfunction "OUT_7") (pintype "output"))
      (node (ref "R10") (pin "1") (pinfunction "1_1") (pintype "passive"))
      (node (ref "R8") (pin "1") (pinfunction "1_1") (pintype "passive"))
    )
    (net (code "30") (name "Net-(IC3C-+IN)") (class "Default")
      (node (ref "C12") (pin "2") (pinfunction "2_2") (pintype "passive"))
      (node (ref "IC3") (pin "10") (pinfunction "+IN_10") (pintype "input"))
      (node (ref "R35") (pin "2") (pinfunction "S_2") (pintype "passive"))
      (node (ref "SJ10") (pin "2") (pinfunction "2_2") (pintype "passive"))
      (node (ref "SJ8") (pin "1") (pinfunction "1_1") (pintype "passive"))
    )
    (net (code "31") (name "Net-(IC3C--IN)") (class "Default")
      (node (ref "C33") (pin "1") (pinfunction "1_1") (pintype "passive"))
      (node (ref "IC3") (pin "9") (pinfunction "-IN_9") (pintype "input"))
      (node (ref "R1") (pin "1") (pinfunction "1_1") (pintype "passive"))
      (node (ref "R2") (pin "2") (pinfunction "2_2") (pintype "passive"))
    )
    (net (code "32") (name "Net-(IC3C-OUT)") (class "Default")
      (node (ref "C33") (pin "2") (pinfunction "2_2") (pintype "passive"))
      (node (ref "IC3") (pin "8") (pinfunction "OUT_8") (pintype "output"))
      (node (ref "R2") (pin "1") (pinfunction "1_1") (pintype "passive"))
      (node (ref "R9") (pin "1") (pinfunction "1_1") (pintype "passive"))
    )
    (net (code "33") (name "Net-(IC3D-+IN)") (class "Default")
      (node (ref "IC3") (pin "12") (pinfunction "+IN_12") (pintype "input"))
      (node (ref "R3") (pin "2") (pinfunction "2_2") (pintype "passive"))
      (node (ref "U$1") (pin "7") (pinfunction "OUT_7") (pintype "input"))
    )
    (net (code "34") (name "Net-(IC3D--IN)") (class "Default")
      (node (ref "C35") (pin "1") (pinfunction "1_1") (pintype "passive"))
      (node (ref "IC3") (pin "13") (pinfunction "-IN_13") (pintype "input"))
      (node (ref "R15") (pin "1") (pinfunction "1_1") (pintype "passive"))
      (node (ref "R16") (pin "2") (pinfunction "2_2") (pintype "passive"))
    )
    (net (code "35") (name "Net-(IC3D-OUT)") (class "Default")
      (node (ref "C35") (pin "2") (pinfunction "2_2") (pintype "passive"))
      (node (ref "C46") (pin "1") (pinfunction "1_1") (pintype "passive"))
      (node (ref "IC3") (pin "14") (pinfunction "OUT_14") (pintype "output"))
      (node (ref "R16") (pin "1") (pinfunction "1_1") (pintype "passive"))
    )
    (net (code "36") (name "Net-(IC4A-+IN)") (class "Default")
      (node (ref "C19") (pin "1") (pinfunction "1_1") (pintype "passive"))
      (node (ref "C5") (pin "1") (pinfunction "1_1") (pintype "passive"))
      (node (ref "IC4") (pin "3") (pinfunction "+IN_3") (pintype "input"))
      (node (ref "R14") (pin "2") (pinfunction "2_2") (pintype "passive"))
      (node (ref "SJ14") (pin "2") (pinfunction "2_2") (pintype "passive"))
    )
    (net (code "37") (name "Net-(IC4A--IN)") (class "Default")
      (node (ref "C29") (pin "1") (pinfunction "1_1") (pintype "passive"))
      (node (ref "IC4") (pin "2") (pinfunction "-IN_2") (pintype "input"))
      (node (ref "R25") (pin "1") (pinfunction "1_1") (pintype "passive"))
      (node (ref "R28") (pin "2") (pinfunction "2_2") (pintype "passive"))
    )
    (net (code "38") (name "Net-(IC4A-OUT)") (class "Default")
      (node (ref "C29") (pin "2") (pinfunction "2_2") (pintype "passive"))
      (node (ref "IC4") (pin "1") (pinfunction "OUT_1") (pintype "output"))
      (node (ref "R25") (pin "2") (pinfunction "2_2") (pintype "passive"))
      (node (ref "SJ14") (pin "1") (pinfunction "1_1") (pintype "passive"))
      (node (ref "U$2") (pin "1") (pinfunction "-IN_1") (pintype "input"))
    )
    (net (code "39") (name "Net-(IC4B-+IN)") (class "Default")
      (node (ref "C18") (pin "2") (pinfunction "2_2") (pintype "passive"))
      (node (ref "C5") (pin "2") (pinfunction "2_2") (pintype "passive"))
      (node (ref "IC4") (pin "5") (pinfunction "+IN_5") (pintype "input"))
      (node (ref "R13") (pin "2") (pinfunction "2_2") (pintype "passive"))
      (node (ref "SJ15") (pin "2") (pinfunction "2_2") (pintype "passive"))
    )
    (net (code "40") (name "Net-(IC4B--IN)") (class "Default")
      (node (ref "C30") (pin "1") (pinfunction "1_1") (pintype "passive"))
      (node (ref "IC4") (pin "6") (pinfunction "-IN_6") (pintype "input"))
      (node (ref "R26") (pin "1") (pinfunction "1_1") (pintype "passive"))
      (node (ref "R28") (pin "1") (pinfunction "1_1") (pintype "passive"))
    )
    (net (code "41") (name "Net-(IC4B-OUT)") (class "Default")
      (node (ref "C30") (pin "2") (pinfunction "2_2") (pintype "passive"))
      (node (ref "IC4") (pin "7") (pinfunction "OUT_7") (pintype "output"))
      (node (ref "R26") (pin "2") (pinfunction "2_2") (pintype "passive"))
      (node (ref "SJ15") (pin "1") (pinfunction "1_1") (pintype "passive"))
      (node (ref "U$2") (pin "4") (pinfunction "+IN_4") (pintype "passive"))
    )
    (net (code "42") (name "Net-(IC5-CV)") (class "Default")
      (node (ref "C7") (pin "2") (pinfunction "2_2") (pintype "passive"))
      (node (ref "IC5") (pin "5") (pinfunction "CV_5") (pintype "input"))
    )
    (net (code "43") (name "Net-(IC5-DIS)") (class "Default")
      (node (ref "IC5") (pin "7") (pinfunction "DIS_7") (pintype "input"))
      (node (ref "R36") (pin "1") (pinfunction "1_1") (pintype "passive"))
      (node (ref "R37") (pin "2") (pinfunction "2_2") (pintype "passive"))
    )
    (net (code "44") (name "Net-(IC5-Q)") (class "Default")
      (node (ref "IC5") (pin "3") (pinfunction "Q_3") (pintype "output"))
      (node (ref "SJ9") (pin "1") (pinfunction "1_1") (pintype "passive"))
    )
    (net (code "45") (name "Net-(IC5-THR)") (class "Default")
      (node (ref "C13") (pin "1") (pinfunction "1_1") (pintype "passive"))
      (node (ref "C6") (pin "2") (pinfunction "2_2") (pintype "passive"))
      (node (ref "IC5") (pin "2") (pinfunction "TR_2") (pintype "input"))
      (node (ref "IC5") (pin "6") (pinfunction "THR_6") (pintype "input"))
      (node (ref "R37") (pin "1") (pinfunction "1_1") (pintype "passive"))
      (node (ref "SJ4") (pin "3") (pinfunction "3_3") (pintype "passive"))
    )
    (net (code "46") (name "Net-(IC6-BYP)") (class "Default")
      (node (ref "C38") (pin "2") (pinfunction "2_2") (pintype "passive"))
      (node (ref "IC6") (pin "4") (pinfunction "BYP_4") (pintype "passive"))
    )
    (net (code "47") (name "Net-(IC6-EN)") (class "Default")
      (node (ref "C37") (pin "2") (pinfunction "2_2") (pintype "passive"))
      (node (ref "D2") (pin "C") (pinfunction "C_C") (pintype "passive"))
      (node (ref "IC6") (pin "1") (pinfunction "IN_1") (pintype "input"))
      (node (ref "IC6") (pin "3") (pinfunction "EN_3") (pintype "input"))
    )
    (net (code "48") (name "Net-(IC6-OUT)") (class "Default")
      (node (ref "C39") (pin "2") (pinfunction "2_2") (pintype "passive"))
      (node (ref "IC6") (pin "5") (pinfunction "OUT_5") (pintype "output"))
      (node (ref "SJ1") (pin "3") (pinfunction "3_3") (pintype "passive"))
    )
    (net (code "49") (name "Net-(IC7-BYP)") (class "Default")
      (node (ref "C32") (pin "1") (pinfunction "1_1") (pintype "passive"))
      (node (ref "IC7") (pin "4") (pinfunction "BYP_4") (pintype "passive"))
    )
    (net (code "50") (name "Net-(IC7-EN)") (class "Default")
      (node (ref "C14") (pin "2") (pinfunction "2_2") (pintype "passive"))
      (node (ref "IC7") (pin "1") (pinfunction "IN_1") (pintype "input"))
      (node (ref "IC7") (pin "3") (pinfunction "EN_3") (pintype "input"))
      (node (ref "R38") (pin "2") (pinfunction "2_2") (pintype "passive"))
    )
    (net (code "51") (name "Net-(IC7-OUT)") (class "Default")
      (node (ref "C32") (pin "2") (pinfunction "2_2") (pintype "passive"))
      (node (ref "IC7") (pin "5") (pinfunction "OUT_5") (pintype "output"))
      (node (ref "SJ16") (pin "2") (pinfunction "2_2") (pintype "passive"))
    )
    (net (code "52") (name "Net-(IOL-Pad1)") (class "Default")
      (node (ref "IOL") (pin "1") (pinfunction "1_1") (pintype "passive"))
      (node (ref "TXD") (pin "1") (pinfunction "1_1") (pintype "passive"))
    )
    (net (code "53") (name "Net-(IOL-Pad2)") (class "Default")
      (node (ref "IOL") (pin "2") (pinfunction "2_2") (pintype "passive"))
      (node (ref "R20") (pin "2") (pinfunction "2_2") (pintype "passive"))
    )
    (net (code "54") (name "Net-(IOL-Pad3)") (class "Default")
      (node (ref "IOL") (pin "3") (pinfunction "3_3") (pintype "passive"))
      (node (ref "R33") (pin "2") (pinfunction "2_2") (pintype "passive"))
    )
    (net (code "55") (name "Net-(IOL-Pad4)") (class "Default")
      (node (ref "IOL") (pin "4") (pinfunction "4_4") (pintype "passive"))
      (node (ref "SJ9") (pin "3") (pinfunction "3_3") (pintype "passive"))
    )
    (net (code "56") (name "Net-(JP2-Pad1)") (class "Default")
      (node (ref "JP2") (pin "1") (pinfunction "1_1") (pintype "passive"))
      (node (ref "SJ6") (pin "3") (pinfunction "3_3") (pintype "passive"))
    )
    (net (code "57") (name "Net-(K1-A)") (class "Default")
      (node (ref "K1") (pin "1") (pinfunction "A_1") (pintype "passive"))
      (node (ref "K2") (pin "1") (pinfunction "A_1") (pintype "passive"))
      (node (ref "R33") (pin "1") (pinfunction "1_1") (pintype "passive"))
    )
    (net (code "58") (name "Net-(K1-DS1)") (class "Default")
      (node (ref "C44") (pin "2") (pinfunction "2_2") (pintype "passive"))
      (node (ref "K1") (pin "4") (pinfunction "DS1_4") (pintype "passive"))
      (node (ref "S2") (pin "1") (pinfunction "S_1") (pintype "passive"))
    )
    (net (code "59") (name "Net-(K2-DS1)") (class "Default")
      (node (ref "C13") (pin "2") (pinfunction "2_2") (pintype "passive"))
      (node (ref "K2") (pin "4") (pinfunction "DS1_4") (pintype "passive"))
      (node (ref "S2") (pin "4") (pinfunction "S_4") (pintype "passive"))
    )
    (net (code "60") (name "Net-(LR-IN1-Pad1)") (class "Default")
      (node (ref "LR-IN1") (pin "1") (pinfunction "1_1") (pintype "passive"))
      (node (ref "R11") (pin "1") (pinfunction "1_1") (pintype "passive"))
    )
    (net (code "61") (name "Net-(LR-IN1-Pad2)") (class "Default")
      (node (ref "LR-IN1") (pin "2") (pinfunction "2_2") (pintype "passive"))
      (node (ref "R14") (pin "1") (pinfunction "1_1") (pintype "passive"))
    )
    (net (code "62") (name "Net-(LR-IN1-Pad3)") (class "Default")
      (node (ref "LR-IN1") (pin "3") (pinfunction "3_3") (pintype "passive"))
      (node (ref "LR-IN1") (pin "4") (pinfunction "4_4") (pintype "passive"))
      (node (ref "SJ6") (pin "2") (pinfunction "2_2") (pintype "passive"))
    )
    (net (code "63") (name "Net-(LR-IN1-Pad5)") (class "Default")
      (node (ref "LR-IN1") (pin "5") (pinfunction "5_5") (pintype "passive"))
      (node (ref "R12") (pin "1") (pinfunction "1_1") (pintype "passive"))
    )
    (net (code "64") (name "Net-(LR-IN1-Pad6)") (class "Default")
      (node (ref "LR-IN1") (pin "6") (pinfunction "6_6") (pintype "passive"))
      (node (ref "R13") (pin "1") (pinfunction "1_1") (pintype "passive"))
    )
    (net (code "65") (name "Net-(POWER-Pad5)") (class "Default")
      (node (ref "POWER") (pin "5") (pinfunction "5_5") (pintype "passive"))
      (node (ref "SJ1") (pin "1") (pinfunction "1_1") (pintype "passive"))
    )
    (net (code "66") (name "Net-(R20-Pad1)") (class "Default")
      (node (ref "R20") (pin "1") (pinfunction "1_1") (pintype "passive"))
      (node (ref "R22") (pin "2") (pinfunction "2_2") (pintype "passive"))
      (node (ref "RXD") (pin "1") (pinfunction "1_1") (pintype "passive"))
    )
    (net (code "67") (name "Net-(R30-Pad1)") (class "Default")
      (node (ref "R30") (pin "1") (pinfunction "1_1") (pintype "passive"))
      (node (ref "R40") (pin "2") (pinfunction "2_2") (pintype "passive"))
    )
    (net (code "68") (name "Net-(R30-Pad2)") (class "Default")
      (node (ref "R30") (pin "2") (pinfunction "2_2") (pintype "passive"))
      (node (ref "R32") (pin "2") (pinfunction "2_2") (pintype "passive"))
    )
    (net (code "69") (name "Net-(R31-Pad2)") (class "Default")
      (node (ref "R31") (pin "2") (pinfunction "2_2") (pintype "passive"))
      (node (ref "R41") (pin "1") (pinfunction "1_1") (pintype "passive"))
    )
    (net (code "70") (name "Net-(R34-A)") (class "Default")
      (node (ref "C25") (pin "2") (pinfunction "2_2") (pintype "passive"))
      (node (ref "R34") (pin "3") (pinfunction "A_3") (pintype "passive"))
      (node (ref "R35") (pin "3") (pinfunction "A_3") (pintype "passive"))
      (node (ref "R39") (pin "2") (pinfunction "2_2") (pintype "passive"))
    )
    (net (code "71") (name "Net-(R34-E)") (class "Default")
      (node (ref "R29") (pin "2") (pinfunction "2_2") (pintype "passive"))
      (node (ref "R34") (pin "1") (pinfunction "E_1") (pintype "passive"))
      (node (ref "R35") (pin "1") (pinfunction "E_1") (pintype "passive"))
      (node (ref "SJ10") (pin "1") (pinfunction "1_1") (pintype "passive"))
      (node (ref "SJ11") (pin "1") (pinfunction "1_1") (pintype "passive"))
    )
    (net (code "72") (name "Net-(SJ4-Pad1)") (class "Default")
      (node (ref "SJ4") (pin "1") (pinfunction "1_1") (pintype "passive"))
      (node (ref "SJ5") (pin "1") (pinfunction "1_1") (pintype "passive"))
      (node (ref "SJ9") (pin "2") (pinfunction "2_2") (pintype "passive"))
    )
    (net (code "73") (name "Net-(U$1-RG1)") (class "Default")
      (node (ref "R5") (pin "2") (pinfunction "2_2") (pintype "passive"))
      (node (ref "U$1") (pin "2") (pinfunction "RG1_2") (pintype "input"))
    )
    (net (code "74") (name "Net-(U$1-RG2)") (class "Default")
      (node (ref "R5") (pin "1") (pinfunction "1_1") (pintype "passive"))
      (node (ref "U$1") (pin "3") (pinfunction "RG2_3") (pintype "input"))
    )
    (net (code "75") (name "Net-(U$2-RG1)") (class "Default")
      (node (ref "R6") (pin "2") (pinfunction "2_2") (pintype "passive"))
      (node (ref "U$2") (pin "2") (pinfunction "RG1_2") (pintype "input"))
    )
    (net (code "76") (name "Net-(U$2-RG2)") (class "Default")
      (node (ref "R6") (pin "1") (pinfunction "1_1") (pintype "passive"))
      (node (ref "U$2") (pin "3") (pinfunction "RG2_3") (pintype "input"))
    )
    (net (code "77") (name "Net-(U$4-CLK)") (class "Default")
      (node (ref "SJ5") (pin "2") (pinfunction "2_2") (pintype "passive"))
      (node (ref "U$4") (pin "8") (pinfunction "CLK_8") (pintype "input"))
    )
    (net (code "78") (name "Net-(U$4-COM)") (class "Default")
      (node (ref "C2") (pin "2") (pinfunction "2_2") (pintype "passive"))
      (node (ref "U$4") (pin "1") (pinfunction "COM_1") (pintype "input"))
      (node (ref "U$4") (pin "6") (pinfunction "OS_6") (pintype "passive"))
    )
    (net (code "79") (name "Net-(U$4-IN)") (class "Default")
      (node (ref "D3") (pin "C") (pinfunction "C_C") (pintype "passive"))
      (node (ref "R9") (pin "2") (pinfunction "2_2") (pintype "passive"))
      (node (ref "U$4") (pin "2") (pinfunction "IN_2") (pintype "input"))
    )
    (net (code "80") (name "Net-(U$4-OUT)") (class "Default")
      (node (ref "R18") (pin "1") (pinfunction "1_1") (pintype "passive"))
      (node (ref "U$4") (pin "5") (pinfunction "OUT_5") (pintype "input"))
    )
    (net (code "81") (name "Net-(U$5-CLK)") (class "Default")
      (node (ref "SJ4") (pin "2") (pinfunction "2_2") (pintype "passive"))
      (node (ref "U$5") (pin "8") (pinfunction "CLK_8") (pintype "input"))
    )
    (net (code "82") (name "Net-(U$5-COM)") (class "Default")
      (node (ref "C3") (pin "2") (pinfunction "2_2") (pintype "passive"))
      (node (ref "U$5") (pin "1") (pinfunction "COM_1") (pintype "input"))
      (node (ref "U$5") (pin "6") (pinfunction "OS_6") (pintype "passive"))
    )
    (net (code "83") (name "Net-(U$5-IN)") (class "Default")
      (node (ref "D1") (pin "C") (pinfunction "C_C") (pintype "passive"))
      (node (ref "R10") (pin "2") (pinfunction "2_2") (pintype "passive"))
      (node (ref "U$5") (pin "2") (pinfunction "IN_2") (pintype "input"))
    )
    (net (code "84") (name "Net-(U$5-OUT)") (class "Default")
      (node (ref "R21") (pin "1") (pinfunction "1_1") (pintype "passive"))
      (node (ref "U$5") (pin "5") (pinfunction "OUT_5") (pintype "input"))
    )
    (net (code "85") (name "V+") (class "Default")
      (node (ref "C22") (pin "2") (pinfunction "2_2") (pintype "passive"))
      (node (ref "C23") (pin "2") (pinfunction "2_2") (pintype "passive"))
      (node (ref "C40") (pin "2") (pinfunction "2_2") (pintype "passive"))
      (node (ref "C42") (pin "1") (pinfunction "1_1") (pintype "passive"))
      (node (ref "C48") (pin "2") (pinfunction "2_2") (pintype "passive"))
      (node (ref "C51") (pin "1") (pinfunction "1_1") (pintype "passive"))
      (node (ref "C9") (pin "1") (pinfunction "1_1") (pintype "passive"))
      (node (ref "IC1") (pin "8") (pinfunction "V+_8") (pintype "power_in"))
      (node (ref "R38") (pin "1") (pinfunction "1_1") (pintype "passive"))
      (node (ref "U$1") (pin "8") (pinfunction "+V_8") (pintype "power_in"))
      (node (ref "U$2") (pin "8") (pinfunction "+V_8") (pintype "power_in"))
      (node (ref "U$7") (pin "6") (pinfunction "+VOUT_6") (pintype "passive"))
    )
    (net (code "86") (name "V-") (class "Default")
      (node (ref "C21") (pin "1") (pinfunction "1_1") (pintype "passive"))
      (node (ref "C27") (pin "1") (pinfunction "1_1") (pintype "passive"))
      (node (ref "C41") (pin "1") (pinfunction "1_1") (pintype "passive"))
      (node (ref "C43") (pin "1") (pinfunction "1_1") (pintype "passive"))
      (node (ref "C49") (pin "2") (pinfunction "2_2") (pintype "passive"))
      (node (ref "C50") (pin "1") (pinfunction "1_1") (pintype "passive"))
      (node (ref "C8") (pin "2") (pinfunction "2_2") (pintype "passive"))
      (node (ref "IC1") (pin "4") (pinfunction "V-_4") (pintype "power_in"))
      (node (ref "U$1") (pin "5") (pinfunction "-V_5") (pintype "power_in"))
      (node (ref "U$2") (pin "5") (pinfunction "-V_5") (pintype "power_in"))
      (node (ref "U$7") (pin "4") (pinfunction "-VOUT_4") (pintype "passive"))
    )
    (net (code "87") (name "VCC") (class "Default")
      (node (ref "C20") (pin "2") (pinfunction "2_2") (pintype "passive"))
      (node (ref "IC5") (pin "4") (pinfunction "R_4") (pintype "input"))
      (node (ref "IC5") (pin "8") (pinfunction "V+_8") (pintype "power_in"))
      (node (ref "R36") (pin "2") (pinfunction "2_2") (pintype "passive"))
      (node (ref "R41") (pin "2") (pinfunction "2_2") (pintype "passive"))
      (node (ref "SJ1") (pin "2") (pinfunction "2_2") (pintype "passive"))
      (node (ref "U$4") (pin "4") (pinfunction "+5V_4") (pintype "power_in"))
      (node (ref "U$4") (pin "7") (pinfunction "/SHDN_7") (pintype "input"))
      (node (ref "U$5") (pin "4") (pinfunction "+5V_4") (pintype "power_in"))
      (node (ref "U$5") (pin "7") (pinfunction "/SHDN_7") (pintype "input"))
      (node (ref "U$7") (pin "1") (pinfunction "+VIN_1") (pintype "passive"))
      (node (ref "VCC") (pin "1") (pinfunction "1_1") (pintype "passive"))
    )
    (net (code "88") (name "VEE") (class "Default")
      (node (ref "C26") (pin "2") (pinfunction "2_2") (pintype "passive"))
      (node (ref "IOH") (pin "8") (pinfunction "8_8") (pintype "passive"))
      (node (ref "R39") (pin "1") (pinfunction "1_1") (pintype "passive"))
      (node (ref "SJ16") (pin "1") (pinfunction "1_1") (pintype "passive"))
    )
    (net (code "89") (name "unconnected-(AD-Pad5)") (class "Default")
      (node (ref "AD") (pin "5") (pinfunction "5_5") (pintype "passive"))
    )
    (net (code "90") (name "unconnected-(AD-Pad6)") (class "Default")
      (node (ref "AD") (pin "6") (pinfunction "6_6") (pintype "passive"))
    )
    (net (code "91") (name "unconnected-(ICSP-Pad1)") (class "Default")
      (node (ref "ICSP") (pin "1") (pinfunction "1_1") (pintype "passive"))
    )
    (net (code "92") (name "unconnected-(ICSP-Pad2)") (class "Default")
      (node (ref "ICSP") (pin "2") (pinfunction "2_2") (pintype "passive"))
    )
    (net (code "93") (name "unconnected-(ICSP-Pad3)") (class "Default")
      (node (ref "ICSP") (pin "3") (pinfunction "3_3") (pintype "passive"))
    )
    (net (code "94") (name "unconnected-(ICSP-Pad4)") (class "Default")
      (node (ref "ICSP") (pin "4") (pinfunction "4_4") (pintype "passive"))
    )
    (net (code "95") (name "unconnected-(ICSP-Pad5)") (class "Default")
      (node (ref "ICSP") (pin "5") (pinfunction "5_5") (pintype "passive"))
    )
    (net (code "96") (name "unconnected-(ICSP-Pad6)") (class "Default")
      (node (ref "ICSP") (pin "6") (pinfunction "6_6") (pintype "passive"))
    )
    (net (code "97") (name "unconnected-(IOH-Pad1)") (class "Default")
      (node (ref "IOH") (pin "1") (pinfunction "1_1") (pintype "passive"))
    )
    (net (code "98") (name "unconnected-(IOH-Pad2)") (class "Default")
      (node (ref "IOH") (pin "2") (pinfunction "2_2") (pintype "passive"))
    )
    (net (code "99") (name "unconnected-(IOH-Pad3)") (class "Default")
      (node (ref "IOH") (pin "3") (pinfunction "3_3") (pintype "passive"))
    )
    (net (code "100") (name "unconnected-(IOH-Pad4)") (class "Default")
      (node (ref "IOH") (pin "4") (pinfunction "4_4") (pintype "passive"))
    )
    (net (code "101") (name "unconnected-(IOH-Pad5)") (class "Default")
      (node (ref "IOH") (pin "5") (pinfunction "5_5") (pintype "passive"))
    )
    (net (code "102") (name "unconnected-(IOH-Pad6)") (class "Default")
      (node (ref "IOH") (pin "6") (pinfunction "6_6") (pintype "passive"))
    )
    (net (code "103") (name "unconnected-(IOH-Pad7)") (class "Default")
      (node (ref "IOH") (pin "7") (pinfunction "7_7") (pintype "passive"))
    )
    (net (code "104") (name "unconnected-(IOH-Pad9)") (class "Default")
      (node (ref "IOH") (pin "9") (pinfunction "9_9") (pintype "passive"))
    )
    (net (code "105") (name "unconnected-(IOH-Pad10)") (class "Default")
      (node (ref "IOH") (pin "10") (pinfunction "10_10") (pintype "passive"))
    )
    (net (code "106") (name "unconnected-(IOL-Pad5)") (class "Default")
      (node (ref "IOL") (pin "5") (pinfunction "5_5") (pintype "passive"))
    )
    (net (code "107") (name "unconnected-(IOL-Pad6)") (class "Default")
      (node (ref "IOL") (pin "6") (pinfunction "6_6") (pintype "passive"))
    )
    (net (code "108") (name "unconnected-(IOL-Pad7)") (class "Default")
      (node (ref "IOL") (pin "7") (pinfunction "7_7") (pintype "passive"))
    )
    (net (code "109") (name "unconnected-(IOL-Pad8)") (class "Default")
      (node (ref "IOL") (pin "8") (pinfunction "8_8") (pintype "passive"))
    )
    (net (code "110") (name "unconnected-(POWER-Pad1)") (class "Default")
      (node (ref "POWER") (pin "1") (pinfunction "1_1") (pintype "passive"))
    )
    (net (code "111") (name "unconnected-(POWER-Pad2)") (class "Default")
      (node (ref "POWER") (pin "2") (pinfunction "2_2") (pintype "passive"))
    )
    (net (code "112") (name "unconnected-(POWER-Pad3)") (class "Default")
      (node (ref "POWER") (pin "3") (pinfunction "3_3") (pintype "passive"))
    )
    (net (code "113") (name "unconnected-(POWER-Pad4)") (class "Default")
      (node (ref "POWER") (pin "4") (pinfunction "4_4") (pintype "passive"))
    )
    (net (code "114") (name "unconnected-(R31-Pad1)") (class "Default")
      (node (ref "R31") (pin "1") (pinfunction "1_1") (pintype "passive"))
    )
    (net (code "115") (name "unconnected-(R32-Pad1)") (class "Default")
      (node (ref "R32") (pin "1") (pinfunction "1_1") (pintype "passive"))
    )
    (net (code "116") (name "unconnected-(R40-Pad1)") (class "Default")
      (node (ref "R40") (pin "1") (pinfunction "1_1") (pintype "passive"))
    )
    (net (code "117") (name "unconnected-(S2A-O-Pad3)") (class "Default")
      (node (ref "S2") (pin "3") (pinfunction "O_3") (pintype "passive"))
    )
    (net (code "118") (name "unconnected-(S2B-O-Pad6)") (class "Default")
      (node (ref "S2") (pin "6") (pinfunction "O_6") (pintype "passive"))
    )
  )
)
